# WINGS_Components.net
KiCad netlist of a schematic drawn in Altium Designer
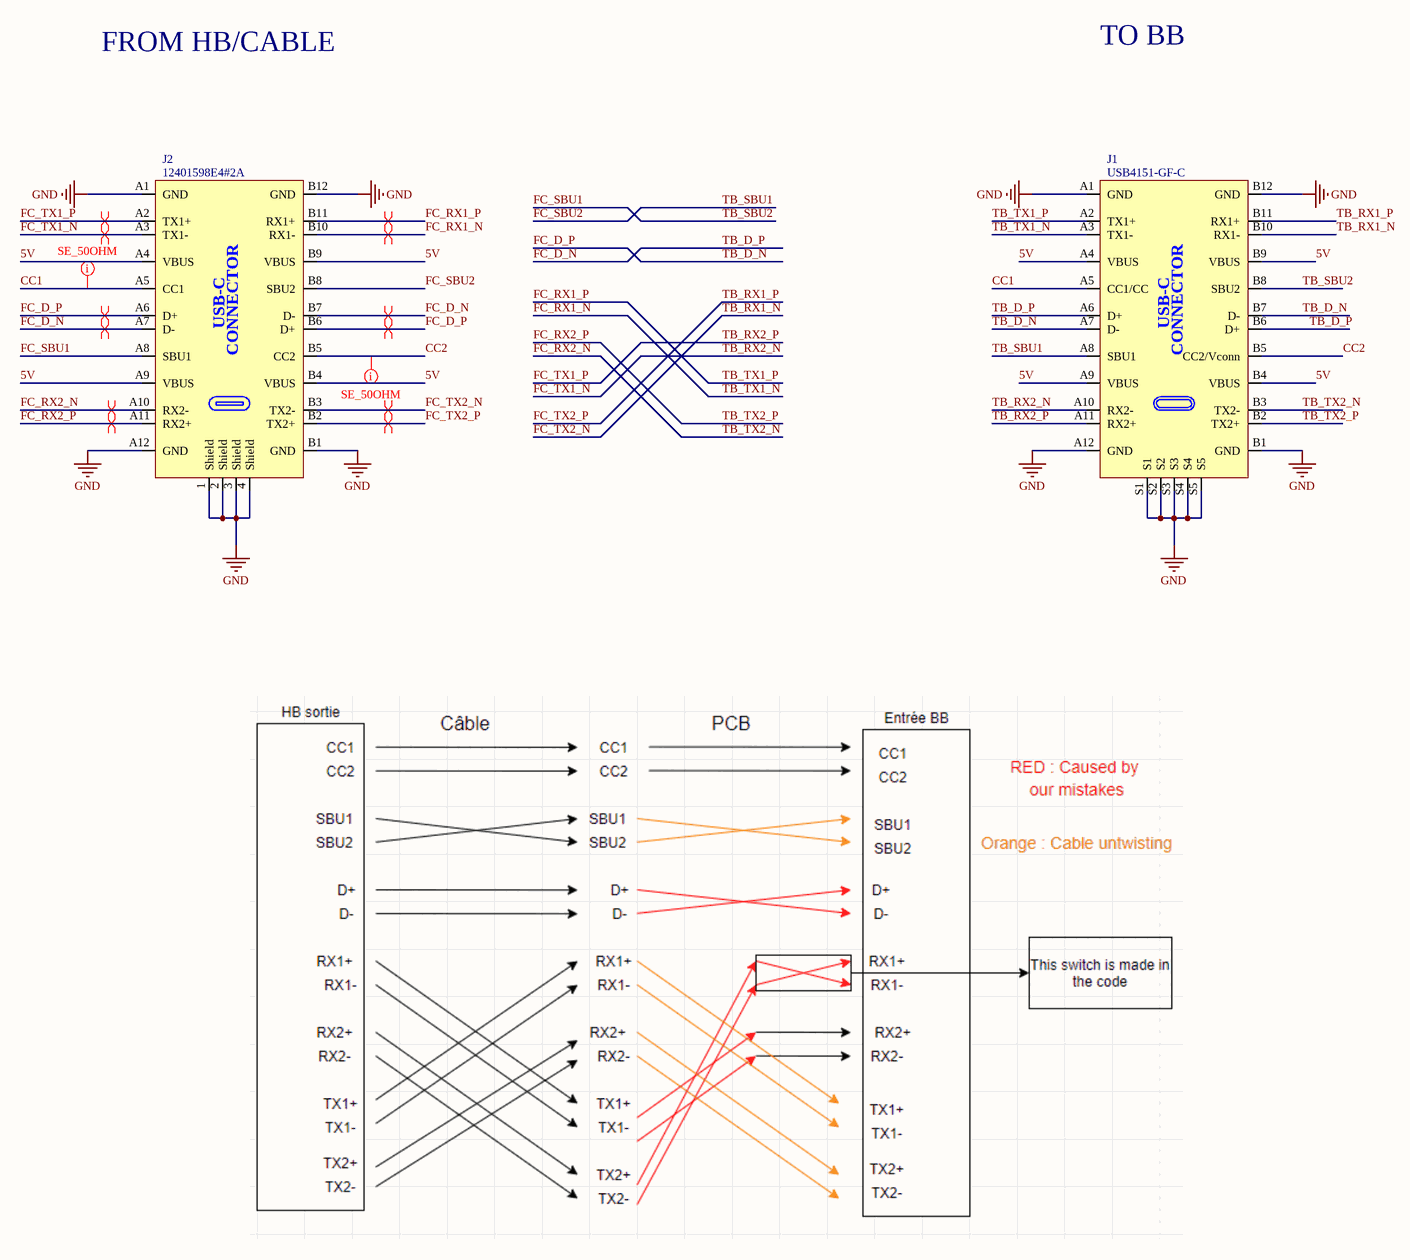
[diagram p0: WINGS_Components.SchDoc]

(export (version "E")
  (design (tool "Eeschema 10.0.6"))
  (components
    (comp (ref "J1")
      (value "USB4151-GF-C")
      (footprint "CON_USB-C_USB4151-GF-C")
      (fields
        (field (name "CREATEDBY/DATE") "Philippe Arsenault/2021-08-17")
        (field (name "VERIFIEDBY") "Hubert Dube/2021-09-02")
      )
      (libsource (lib "SWARMUS_LIB") (part "CON_USB_3.2_TypeC_USB4151-GF-C"))
    )
    (comp (ref "J2")
      (value "12401598E4#2A")
      (footprint "CON_USB_3.2_TypeC_12401598E4#2A")
      (description "CON_USB - USB 3.2 Gen 2 (USB 3.1 Gen 2, Superspeed + (USB 3.1)) 24 pos Receptacle - R/A")
      (fields
        (field (name "CREATEDBY/DATE") "Louis-Daniel Gaulin / 07-04-2021")
        (field (name "VERIFIEDBY") "Philippe Arsenault/2021-04-08")
      )
      (libsource (lib "SWARMUS_LIB") (part "CON_USB_3.2_TypeC_12401598E4#2A"))
    )
  )
  (nets
    (net (code "1") (name "/5V") (class "Default")
      (node (ref "J1") (pin "A4") (pinfunction "VBUS_A4") (pintype "passive"))
      (node (ref "J1") (pin "A9") (pinfunction "VBUS_A9") (pintype "passive"))
      (node (ref "J1") (pin "B4") (pinfunction "VBUS_B4") (pintype "passive"))
      (node (ref "J1") (pin "B9") (pinfunction "VBUS_B9") (pintype "passive"))
      (node (ref "J2") (pin "A4") (pinfunction "VBUS_A4") (pintype "passive"))
      (node (ref "J2") (pin "A9") (pinfunction "VBUS_A9") (pintype "passive"))
      (node (ref "J2") (pin "B4") (pinfunction "VBUS_B4") (pintype "passive"))
      (node (ref "J2") (pin "B9") (pinfunction "VBUS_B9") (pintype "passive"))
    )
    (net (code "2") (name "/CC1") (class "Default")
      (node (ref "J1") (pin "A5") (pinfunction "CC1/CC_A5") (pintype "passive"))
      (node (ref "J2") (pin "A5") (pinfunction "CC1_A5") (pintype "passive"))
    )
    (net (code "3") (name "/CC2") (class "Default")
      (node (ref "J1") (pin "B5") (pinfunction "CC2/Vconn_B5") (pintype "passive"))
      (node (ref "J2") (pin "B5") (pinfunction "CC2_B5") (pintype "passive"))
    )
    (net (code "4") (name "/FC_D_N") (class "Default")
      (node (ref "J1") (pin "A6") (pinfunction "D+_A6") (pintype "passive"))
      (node (ref "J1") (pin "B6") (pinfunction "D+_B6") (pintype "passive"))
      (node (ref "J2") (pin "A7") (pinfunction "D-_A7") (pintype "passive"))
      (node (ref "J2") (pin "B7") (pinfunction "D-_B7") (pintype "passive"))
    )
    (net (code "5") (name "/FC_D_P") (class "Default")
      (node (ref "J1") (pin "A7") (pinfunction "D-_A7") (pintype "passive"))
      (node (ref "J1") (pin "B7") (pinfunction "D-_B7") (pintype "passive"))
      (node (ref "J2") (pin "A6") (pinfunction "D+_A6") (pintype "passive"))
      (node (ref "J2") (pin "B6") (pinfunction "D+_B6") (pintype "passive"))
    )
    (net (code "6") (name "/FC_RX1_N") (class "Default")
      (node (ref "J1") (pin "A3") (pinfunction "TX1-_A3") (pintype "passive"))
      (node (ref "J2") (pin "B10") (pinfunction "RX1-_B10") (pintype "passive"))
    )
    (net (code "7") (name "/FC_RX1_P") (class "Default")
      (node (ref "J1") (pin "A2") (pinfunction "TX1+_A2") (pintype "passive"))
      (node (ref "J2") (pin "B11") (pinfunction "RX1+_B11") (pintype "passive"))
    )
    (net (code "8") (name "/FC_RX2_N") (class "Default")
      (node (ref "J1") (pin "B3") (pinfunction "TX2-_B3") (pintype "passive"))
      (node (ref "J2") (pin "A10") (pinfunction "RX2-_A10") (pintype "passive"))
    )
    (net (code "9") (name "/FC_RX2_P") (class "Default")
      (node (ref "J1") (pin "B2") (pinfunction "TX2+_B2") (pintype "passive"))
      (node (ref "J2") (pin "A11") (pinfunction "RX2+_A11") (pintype "passive"))
    )
    (net (code "10") (name "/FC_SBU1") (class "Default")
      (node (ref "J1") (pin "B8") (pinfunction "SBU2_B8") (pintype "passive"))
      (node (ref "J2") (pin "A8") (pinfunction "SBU1_A8") (pintype "passive"))
    )
    (net (code "11") (name "/FC_SBU2") (class "Default")
      (node (ref "J1") (pin "A8") (pinfunction "SBU1_A8") (pintype "passive"))
      (node (ref "J2") (pin "B8") (pinfunction "SBU2_B8") (pintype "passive"))
    )
    (net (code "12") (name "/FC_TX1_N") (class "Default")
      (node (ref "J1") (pin "A10") (pinfunction "RX2-_A10") (pintype "passive"))
      (node (ref "J2") (pin "A3") (pinfunction "TX1-_A3") (pintype "passive"))
    )
    (net (code "13") (name "/FC_TX1_P") (class "Default")
      (node (ref "J1") (pin "A11") (pinfunction "RX2+_A11") (pintype "passive"))
      (node (ref "J2") (pin "A2") (pinfunction "TX1+_A2") (pintype "passive"))
    )
    (net (code "14") (name "/FC_TX2_N") (class "Default")
      (node (ref "J1") (pin "B10") (pinfunction "RX1-_B10") (pintype "passive"))
      (node (ref "J2") (pin "B3") (pinfunction "TX2-_B3") (pintype "passive"))
    )
    (net (code "15") (name "/FC_TX2_P") (class "Default")
      (node (ref "J1") (pin "B11") (pinfunction "RX1+_B11") (pintype "passive"))
      (node (ref "J2") (pin "B2") (pinfunction "TX2+_B2") (pintype "passive"))
    )
    (net (code "16") (name "GND") (class "Default")
      (node (ref "J1") (pin "A1") (pinfunction "GND_A1") (pintype "passive"))
      (node (ref "J1") (pin "A12") (pinfunction "GND_A12") (pintype "passive"))
      (node (ref "J1") (pin "B1") (pinfunction "GND_B1") (pintype "passive"))
      (node (ref "J1") (pin "B12") (pinfunction "GND_B12") (pintype "passive"))
      (node (ref "J1") (pin "S1") (pinfunction "S1_S1") (pintype "passive"))
      (node (ref "J1") (pin "S2") (pinfunction "S2_S2") (pintype "passive"))
      (node (ref "J1") (pin "S3") (pinfunction "S3_S3") (pintype "passive"))
      (node (ref "J1") (pin "S4") (pinfunction "S4_S4") (pintype "passive"))
      (node (ref "J1") (pin "S5") (pinfunction "S5_S5") (pintype "passive"))
      (node (ref "J2") (pin "1") (pinfunction "Shield_1") (pintype "passive"))
      (node (ref "J2") (pin "2") (pinfunction "Shield_2") (pintype "passive"))
      (node (ref "J2") (pin "3") (pinfunction "Shield_3") (pintype "passive"))
      (node (ref "J2") (pin "4") (pinfunction "Shield_4") (pintype "passive"))
      (node (ref "J2") (pin "A1") (pinfunction "GND_A1") (pintype "passive"))
      (node (ref "J2") (pin "A12") (pinfunction "GND_A12") (pintype "passive"))
      (node (ref "J2") (pin "B1") (pinfunction "GND_B1") (pintype "passive"))
      (node (ref "J2") (pin "B12") (pinfunction "GND_B12") (pintype "passive"))
    )
  )
)
